# OpAmpNSD.net
KiCad netlist of a schematic drawn in Altium Designer
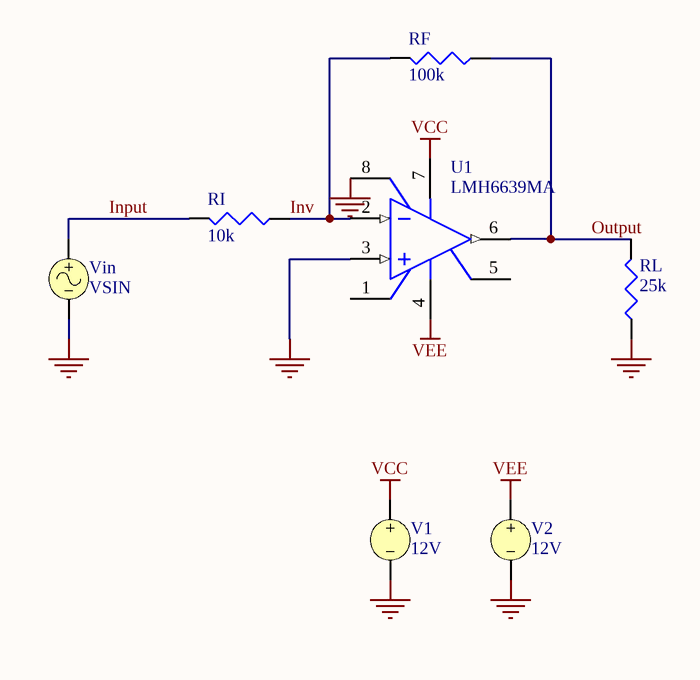
[diagram p0: OpAmpNSD.schdoc]

(export (version "E")
  (design (tool "Eeschema 10.0.6"))
  (components
    (comp (ref "RF") (value "100k") (description "Resistor") (libsource (lib "*") (part "RES")))
    (comp (ref "RI") (value "10k") (description "Resistor") (libsource (lib "*") (part "RES")))
    (comp (ref "RL") (value "25k") (description "Resistor") (libsource (lib "") (part "RES_1")))
    (comp (ref "U1")
      (value "LMH6639MA")
      (footprint "M08A_N")
      (description "190MHz Rail-to-Rail Output Amplifier with Disable")
      (fields
        (field (name "MANUFACTURER") "National Semiconductor")
        (field (name "DIGIKEYPARTNUMBER") "LMH6639MA-ND")
        (field (name "PUBLISHER") "Altium Limited")
      )
      (libsource (lib "NSC Amplifier with SIM models") (part "LMH6639MA"))
    )
    (comp (ref "V1") (value "12V") (description "Voltage Source") (libsource (lib "*") (part "VSRC")))
    (comp (ref "V2")
      (value "12V")
      (description "Voltage Source")
      (fields (field (name "Comment") "-12V"))
      (libsource (lib "*") (part "VSRC"))
    )
    (comp (ref "Vin")
      (value "VSIN")
      (description "Sinusoidal Voltage Source")
      (libsource (lib "*") (part "VSIN"))
    )
  )
  (nets
    (net (code "1") (name "/Input") (class "Default")
      (node (ref "RI") (pin "1") (pinfunction "TOP_1") (pintype "passive"))
      (node (ref "Vin") (pin "1") (pinfunction "1_1") (pintype "passive"))
    )
    (net (code "2") (name "/Inv") (class "Default")
      (node (ref "RF") (pin "1") (pinfunction "TOP_1") (pintype "passive"))
      (node (ref "RI") (pin "2") (pinfunction "BOT_2") (pintype "passive"))
      (node (ref "U1") (pin "2") (pinfunction "IN-_2") (pintype "input"))
    )
    (net (code "3") (name "/Output") (class "Default")
      (node (ref "RF") (pin "2") (pinfunction "BOT_2") (pintype "passive"))
      (node (ref "RL") (pin "1") (pinfunction "TOP_1") (pintype "passive"))
      (node (ref "U1") (pin "6") (pinfunction "OUT_6") (pintype "output"))
    )
    (net (code "4") (name "GND") (class "Default")
      (node (ref "RL") (pin "2") (pinfunction "BOT_2") (pintype "passive"))
      (node (ref "U1") (pin "3") (pinfunction "IN+_3") (pintype "input"))
      (node (ref "U1") (pin "8") (pinfunction "~{SD}_8") (pintype "passive"))
      (node (ref "V1") (pin "2") (pinfunction "2_2") (pintype "passive"))
      (node (ref "V2") (pin "2") (pinfunction "2_2") (pintype "passive"))
      (node (ref "Vin") (pin "2") (pinfunction "2_2") (pintype "passive"))
    )
    (net (code "5") (name "VCC") (class "Default")
      (node (ref "U1") (pin "7") (pinfunction "V+_7") (pintype "power_in"))
      (node (ref "V1") (pin "1") (pinfunction "1_1") (pintype "passive"))
    )
    (net (code "6") (name "VEE") (class "Default")
      (node (ref "U1") (pin "4") (pinfunction "V-_4") (pintype "power_in"))
      (node (ref "V2") (pin "1") (pinfunction "1_1") (pintype "passive"))
    )
    (net (code "7") (name "unconnected-(U1-NC-Pad1)") (class "Default")
      (node (ref "U1") (pin "1") (pinfunction "NC_1") (pintype "passive"))
    )
    (net (code "8") (name "unconnected-(U1-NC-Pad5)") (class "Default")
      (node (ref "U1") (pin "5") (pinfunction "NC_5") (pintype "passive"))
    )
  )
)
